# zhili_v1_0.net
KiCad netlist of a schematic drawn in Altium Designer
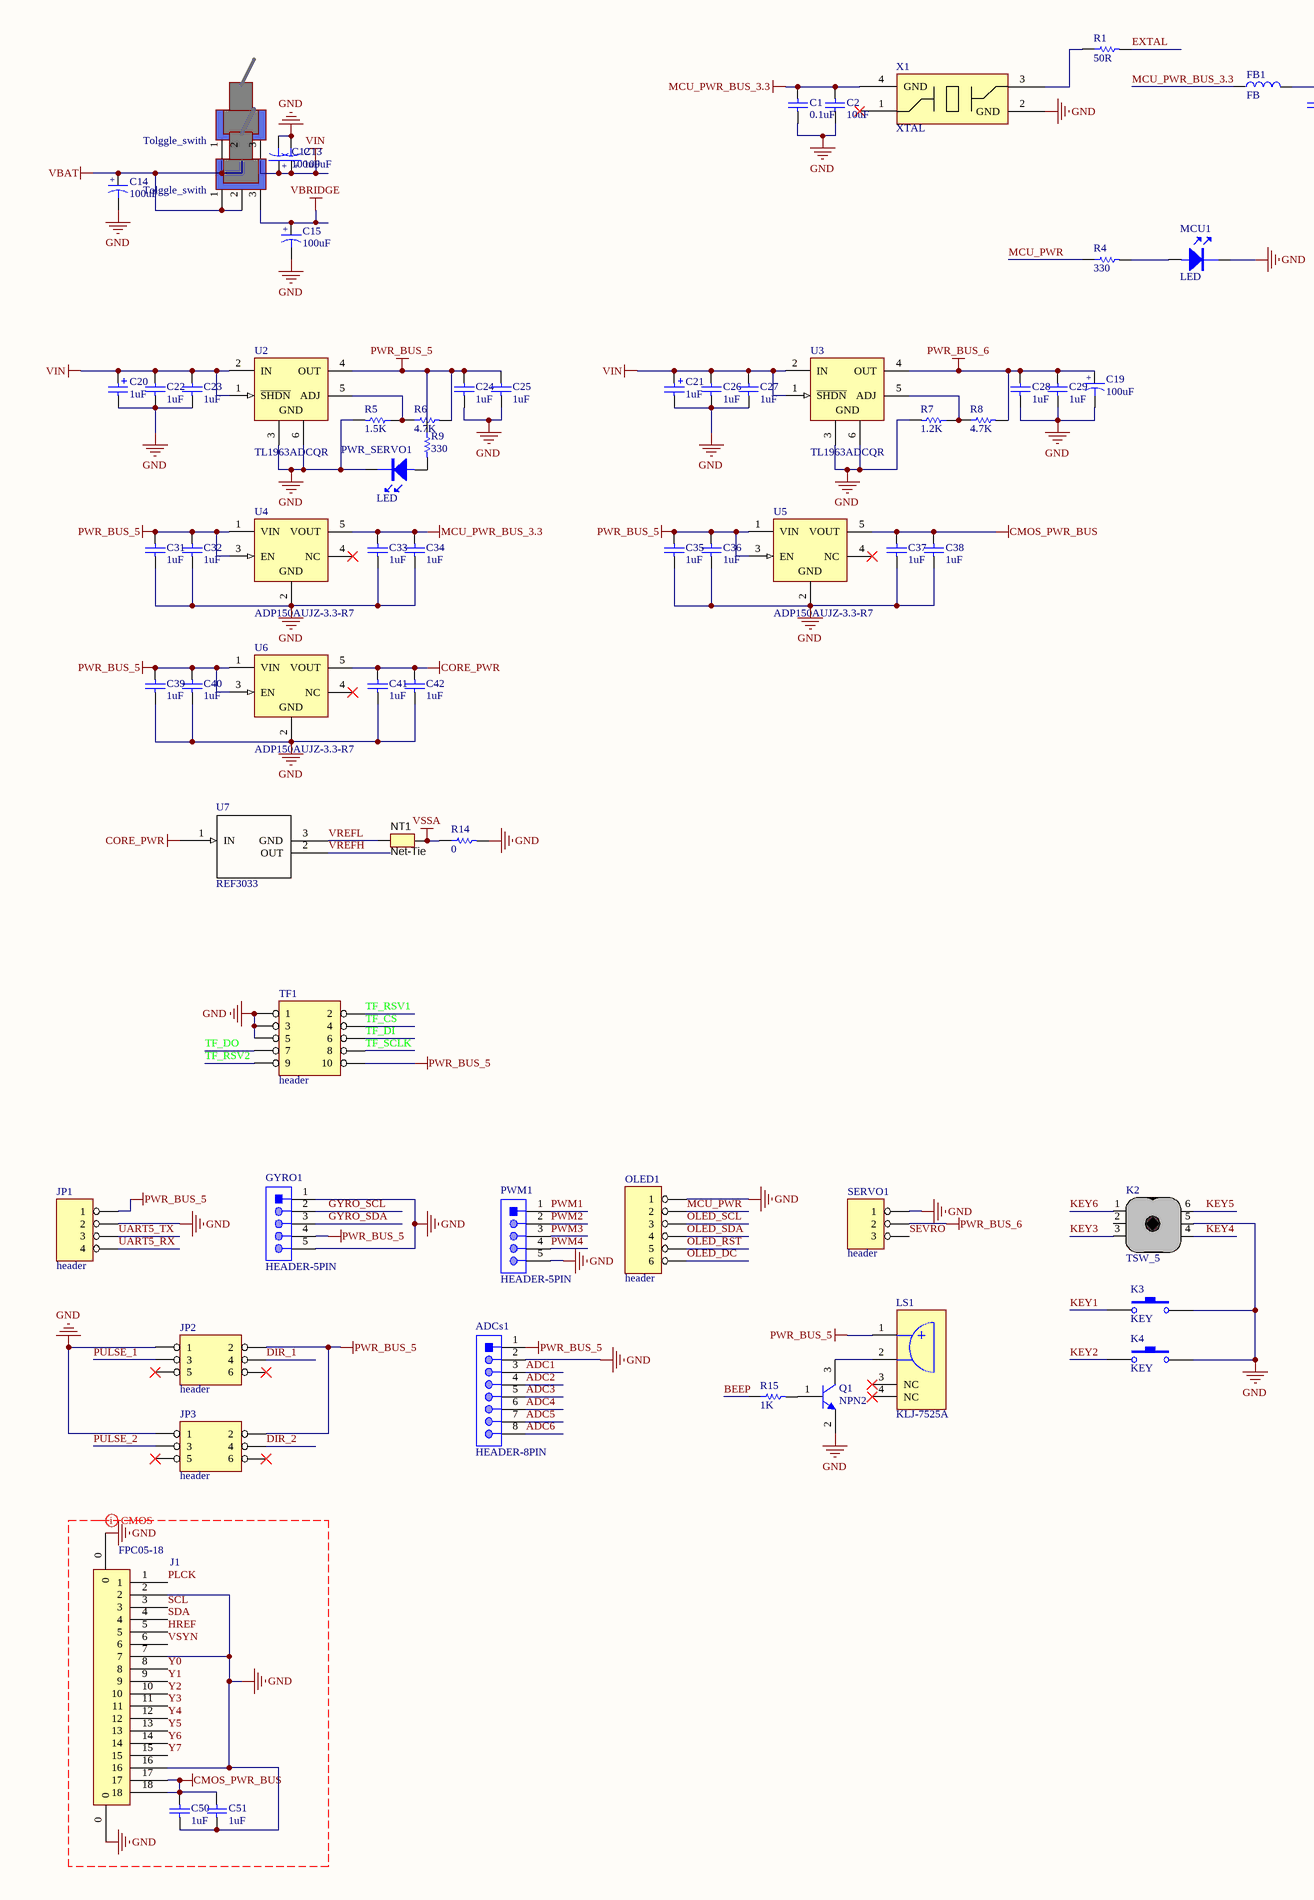
[diagram p0: zhili_v1.0.SchDoc, left]
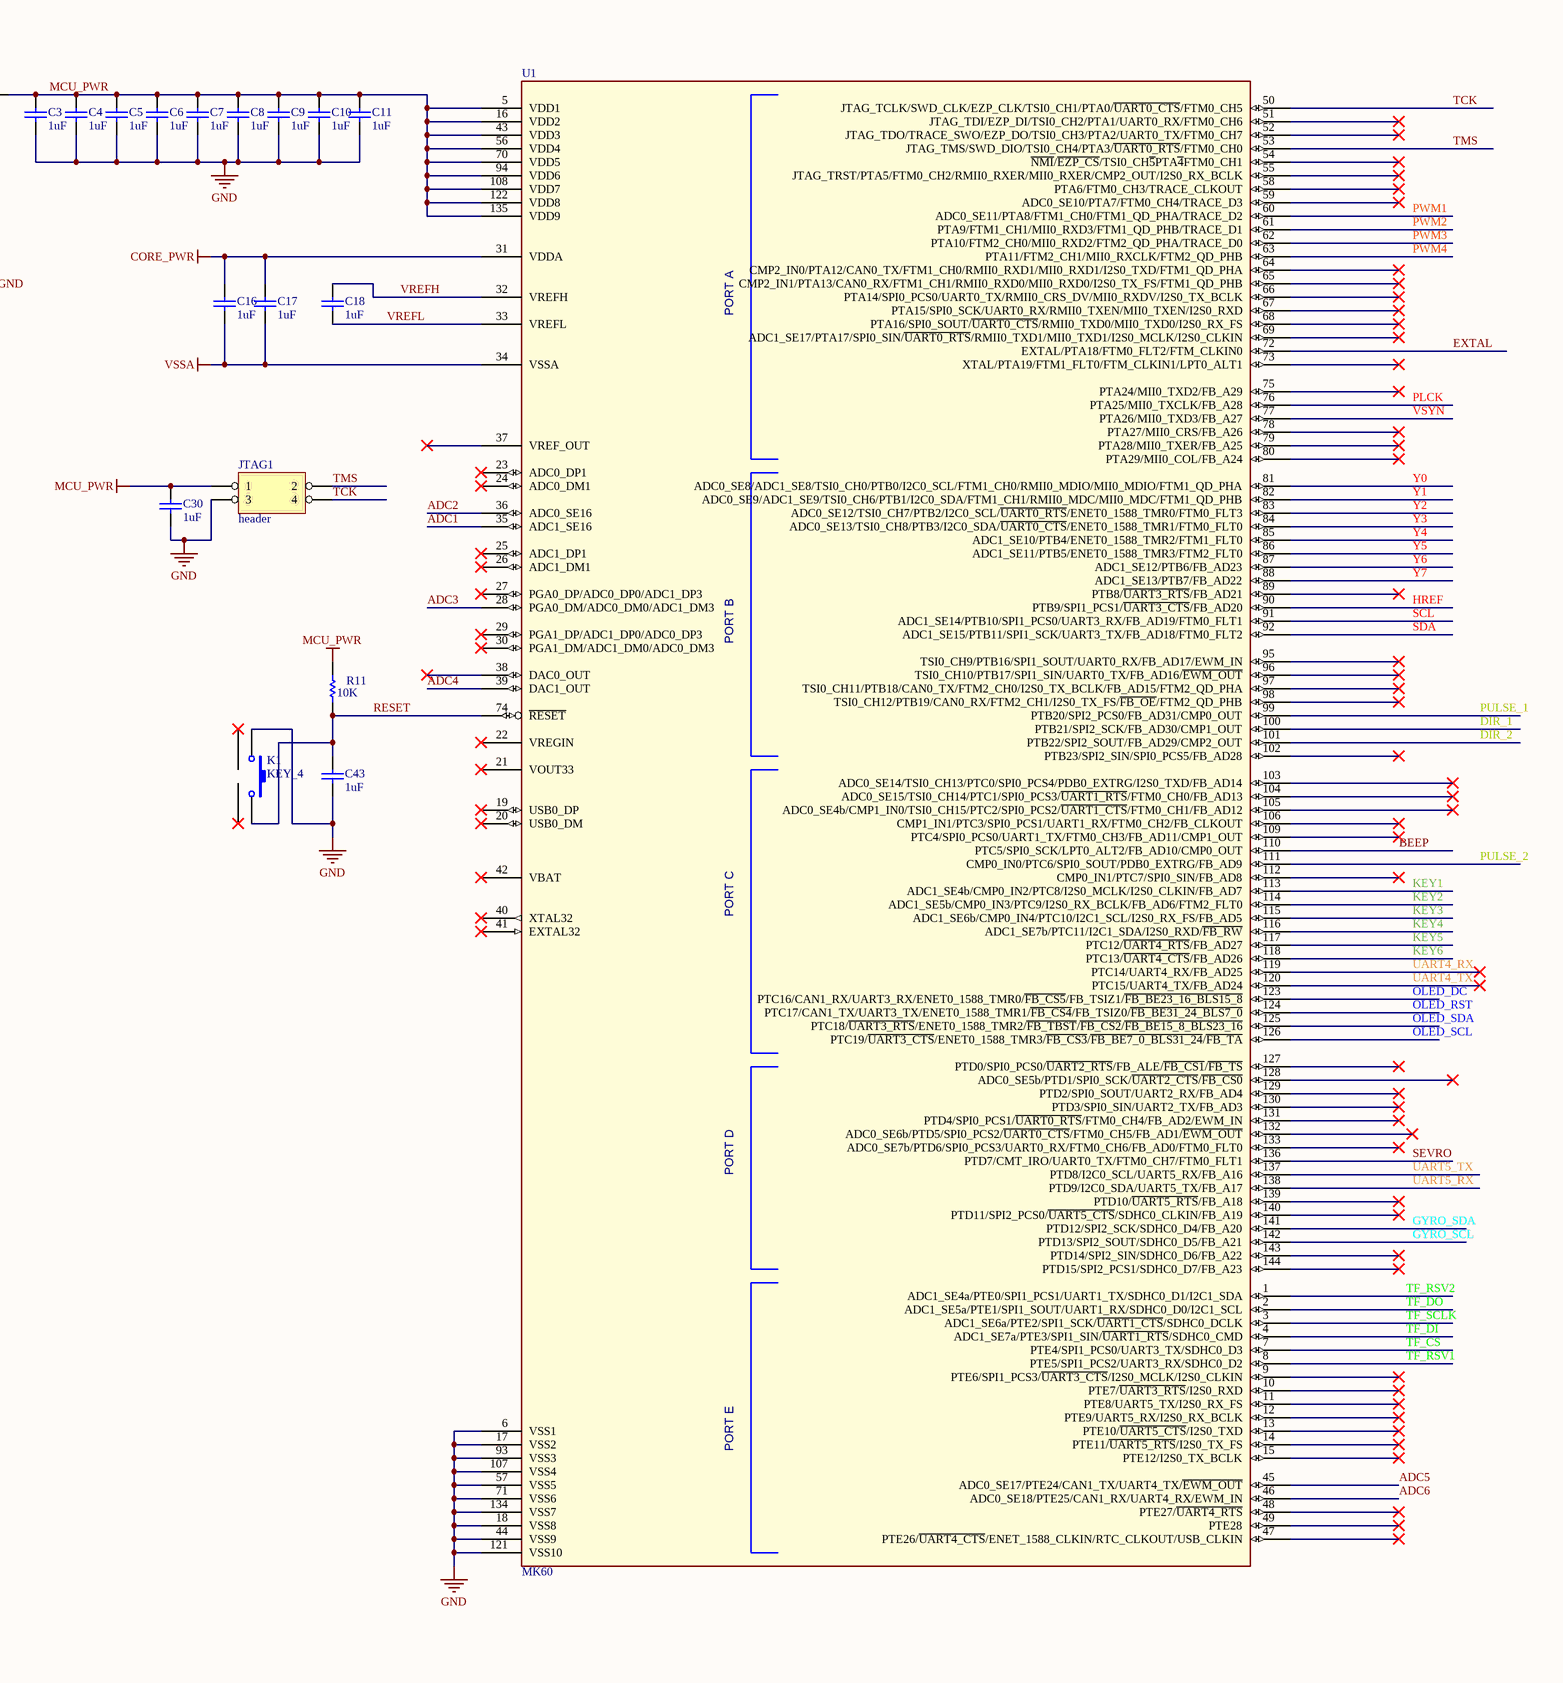
[diagram p1: zhili_v1.0.SchDoc, right]

(export (version "E")
  (design (tool "Eeschema 10.0.6"))
  (components
    (comp (ref "ADCs1")
      (value "HEADER-8PIN")
      (footprint "HEADER_8P_1.25_RT")
      (libsource (lib "My Footprint") (part "HEADER-8PIN"))
    )
    (comp (ref "C1")
      (value "0.1uF")
      (footprint "0603_C")
      (description "Capacitor")
      (fields (field (name "PUBLISHER") "Altium Limited"))
      (libsource (lib "My Footprint") (part "CAP"))
    )
    (comp (ref "C2")
      (value "10uF")
      (footprint "0603_C")
      (description "Capacitor")
      (fields (field (name "PUBLISHER") "Altium Limited"))
      (libsource (lib "My Footprint") (part "CAP"))
    )
    (comp (ref "C3")
      (value "1uF")
      (footprint "0603_C")
      (description "Capacitor")
      (fields (field (name "PUBLISHER") "Altium Limited"))
      (libsource (lib "My Footprint") (part "CAP"))
    )
    (comp (ref "C4")
      (value "1uF")
      (footprint "0603_C")
      (description "Capacitor")
      (fields (field (name "PUBLISHER") "Altium Limited"))
      (libsource (lib "My Footprint") (part "CAP"))
    )
    (comp (ref "C5")
      (value "1uF")
      (footprint "0603_C")
      (description "Capacitor")
      (fields (field (name "PUBLISHER") "Altium Limited"))
      (libsource (lib "My Footprint") (part "CAP"))
    )
    (comp (ref "C6")
      (value "1uF")
      (footprint "0603_C")
      (description "Capacitor")
      (fields (field (name "PUBLISHER") "Altium Limited"))
      (libsource (lib "My Footprint") (part "CAP"))
    )
    (comp (ref "C7")
      (value "1uF")
      (footprint "0603_C")
      (description "Capacitor")
      (fields (field (name "PUBLISHER") "Altium Limited"))
      (libsource (lib "My Footprint") (part "CAP"))
    )
    (comp (ref "C8")
      (value "1uF")
      (footprint "0603_C")
      (description "Capacitor")
      (fields (field (name "PUBLISHER") "Altium Limited"))
      (libsource (lib "My Footprint") (part "CAP"))
    )
    (comp (ref "C9")
      (value "1uF")
      (footprint "0603_C")
      (description "Capacitor")
      (fields (field (name "PUBLISHER") "Altium Limited"))
      (libsource (lib "My Footprint") (part "CAP"))
    )
    (comp (ref "C10")
      (value "1uF")
      (footprint "0603_C")
      (description "Capacitor")
      (fields (field (name "PUBLISHER") "Altium Limited"))
      (libsource (lib "My Footprint") (part "CAP"))
    )
    (comp (ref "C11")
      (value "1uF")
      (footprint "0603_C")
      (description "Capacitor")
      (fields (field (name "PUBLISHER") "Altium Limited"))
      (libsource (lib "My Footprint") (part "CAP"))
    )
    (comp (ref "C12")
      (value "100uF")
      (footprint "C6.3X6.3")
      (libsource (lib "PCB_Project1") (part "Cap_polar"))
    )
    (comp (ref "C13")
      (value "100uF")
      (footprint "C6.3X6.3")
      (libsource (lib "PCB_Project1") (part "Cap_polar"))
    )
    (comp (ref "C14")
      (value "100uF")
      (footprint "CAP 10 x 12")
      (libsource (lib "PCB_Project1") (part "Cap_polar"))
    )
    (comp (ref "C15")
      (value "100uF")
      (footprint "C6.3X6.3")
      (libsource (lib "PCB_Project1") (part "Cap_polar"))
    )
    (comp (ref "C16")
      (value "1uF")
      (footprint "0603_C")
      (description "Capacitor")
      (fields (field (name "PUBLISHER") "Altium Limited"))
      (libsource (lib "My Footprint") (part "CAP"))
    )
    (comp (ref "C17")
      (value "1uF")
      (footprint "0603_C")
      (description "Capacitor")
      (fields (field (name "PUBLISHER") "Altium Limited"))
      (libsource (lib "My Footprint") (part "CAP"))
    )
    (comp (ref "C18")
      (value "1uF")
      (footprint "0603_C")
      (description "Capacitor")
      (fields (field (name "PUBLISHER") "Altium Limited"))
      (libsource (lib "My Footprint") (part "CAP"))
    )
    (comp (ref "C19")
      (value "100uF")
      (footprint "C6.3X6.3")
      (libsource (lib "PCB_Project1") (part "Cap_polar"))
    )
    (comp (ref "C20")
      (value "1uF")
      (footprint "CAPC6032C")
      (description "Capacitor")
      (fields (field (name "PUBLISHER") "Altium Limited"))
      (libsource (lib "My Footprint") (part "CAP_tan"))
    )
    (comp (ref "C21")
      (value "1uF")
      (footprint "CAPC6032C")
      (description "Capacitor")
      (fields (field (name "PUBLISHER") "Altium Limited"))
      (libsource (lib "My Footprint") (part "CAP_tan"))
    )
    (comp (ref "C22")
      (value "1uF")
      (footprint "0603_C")
      (description "Capacitor")
      (fields (field (name "PUBLISHER") "Altium Limited"))
      (libsource (lib "My Footprint") (part "CAP"))
    )
    (comp (ref "C23")
      (value "1uF")
      (footprint "0603_C")
      (description "Capacitor")
      (fields (field (name "PUBLISHER") "Altium Limited"))
      (libsource (lib "My Footprint") (part "CAP"))
    )
    (comp (ref "C24")
      (value "1uF")
      (footprint "0603_C")
      (description "Capacitor")
      (fields (field (name "PUBLISHER") "Altium Limited"))
      (libsource (lib "My Footprint") (part "CAP"))
    )
    (comp (ref "C25")
      (value "1uF")
      (footprint "0603_C")
      (description "Capacitor")
      (fields (field (name "PUBLISHER") "Altium Limited"))
      (libsource (lib "My Footprint") (part "CAP"))
    )
    (comp (ref "C26")
      (value "1uF")
      (footprint "0603_C")
      (description "Capacitor")
      (fields (field (name "PUBLISHER") "Altium Limited"))
      (libsource (lib "My Footprint") (part "CAP"))
    )
    (comp (ref "C27")
      (value "1uF")
      (footprint "0603_C")
      (description "Capacitor")
      (fields (field (name "PUBLISHER") "Altium Limited"))
      (libsource (lib "My Footprint") (part "CAP"))
    )
    (comp (ref "C28")
      (value "1uF")
      (footprint "0603_C")
      (description "Capacitor")
      (fields (field (name "PUBLISHER") "Altium Limited"))
      (libsource (lib "My Footprint") (part "CAP"))
    )
    (comp (ref "C29")
      (value "1uF")
      (footprint "0603_C")
      (description "Capacitor")
      (fields (field (name "PUBLISHER") "Altium Limited"))
      (libsource (lib "My Footprint") (part "CAP"))
    )
    (comp (ref "C30")
      (value "1uF")
      (footprint "0603_C")
      (description "Capacitor")
      (fields (field (name "PUBLISHER") "Altium Limited"))
      (libsource (lib "My Footprint") (part "CAP"))
    )
    (comp (ref "C31")
      (value "1uF")
      (footprint "0805_c")
      (description "Capacitor")
      (fields (field (name "PUBLISHER") "Altium Limited"))
      (libsource (lib "My Footprint") (part "CAP"))
    )
    (comp (ref "C32")
      (value "1uF")
      (footprint "0603_C")
      (description "Capacitor")
      (fields (field (name "PUBLISHER") "Altium Limited"))
      (libsource (lib "My Footprint") (part "CAP"))
    )
    (comp (ref "C33")
      (value "1uF")
      (footprint "0805_c")
      (description "Capacitor")
      (fields (field (name "PUBLISHER") "Altium Limited"))
      (libsource (lib "My Footprint") (part "CAP"))
    )
    (comp (ref "C34")
      (value "1uF")
      (footprint "0603_C")
      (description "Capacitor")
      (fields (field (name "PUBLISHER") "Altium Limited"))
      (libsource (lib "My Footprint") (part "CAP"))
    )
    (comp (ref "C35")
      (value "1uF")
      (footprint "0805_c")
      (description "Capacitor")
      (fields (field (name "PUBLISHER") "Altium Limited"))
      (libsource (lib "My Footprint") (part "CAP"))
    )
    (comp (ref "C36")
      (value "1uF")
      (footprint "0603_C")
      (description "Capacitor")
      (fields (field (name "PUBLISHER") "Altium Limited"))
      (libsource (lib "My Footprint") (part "CAP"))
    )
    (comp (ref "C37")
      (value "1uF")
      (footprint "0805_c")
      (description "Capacitor")
      (fields (field (name "PUBLISHER") "Altium Limited"))
      (libsource (lib "My Footprint") (part "CAP"))
    )
    (comp (ref "C38")
      (value "1uF")
      (footprint "0603_C")
      (description "Capacitor")
      (fields (field (name "PUBLISHER") "Altium Limited"))
      (libsource (lib "My Footprint") (part "CAP"))
    )
    (comp (ref "C39")
      (value "1uF")
      (footprint "0805_c")
      (description "Capacitor")
      (fields (field (name "PUBLISHER") "Altium Limited"))
      (libsource (lib "My Footprint") (part "CAP"))
    )
    (comp (ref "C40")
      (value "1uF")
      (footprint "0603_C")
      (description "Capacitor")
      (fields (field (name "PUBLISHER") "Altium Limited"))
      (libsource (lib "My Footprint") (part "CAP"))
    )
    (comp (ref "C41")
      (value "1uF")
      (footprint "0805_c")
      (description "Capacitor")
      (fields (field (name "PUBLISHER") "Altium Limited"))
      (libsource (lib "My Footprint") (part "CAP"))
    )
    (comp (ref "C42")
      (value "1uF")
      (footprint "0603_C")
      (description "Capacitor")
      (fields (field (name "PUBLISHER") "Altium Limited"))
      (libsource (lib "My Footprint") (part "CAP"))
    )
    (comp (ref "C43")
      (value "1uF")
      (footprint "0603_C")
      (description "Capacitor")
      (fields (field (name "PUBLISHER") "Altium Limited"))
      (libsource (lib "My Footprint") (part "CAP"))
    )
    (comp (ref "C50")
      (value "1uF")
      (footprint "0603_C")
      (description "Capacitor")
      (fields (field (name "PUBLISHER") "Altium Limited"))
      (libsource (lib "My Footprint") (part "CAP"))
    )
    (comp (ref "C51")
      (value "1uF")
      (footprint "0603_C")
      (description "Capacitor")
      (fields (field (name "PUBLISHER") "Altium Limited"))
      (libsource (lib "My Footprint") (part "CAP"))
    )
    (comp (ref "DRV1")
      (value "Tolggle_swith")
      (footprint "TOGGLE SWICH STAND")
      (libsource (lib "通用驱动") (part "Tolggle_swith"))
    )
    (comp (ref "FB1")
      (value "FB")
      (footprint "0805")
      (description "磁珠")
      (libsource (lib "My Footprint") (part "FB"))
    )
    (comp (ref "GYRO1")
      (value "HEADER-5PIN")
      (footprint "HEADER_5P_1.25_RT")
      (libsource (lib "My Footprint") (part "HEADER-5PIN"))
    )
    (comp (ref "J1") (value "FPC05-18") (footprint "FPC_18_VER") (libsource (lib "FPC18") (part "FPC05-18")))
    (comp (ref "JP1")
      (value "header")
      (footprint "header4")
      (libsource (lib "My Footprint") (part "HEADER 4"))
    )
    (comp (ref "JP2")
      (value "header")
      (footprint "header2X3")
      (libsource (lib "My Footprint") (part "HEADER 3X2"))
    )
    (comp (ref "JP3")
      (value "header")
      (footprint "header2X3")
      (libsource (lib "My Footprint") (part "HEADER 3X2"))
    )
    (comp (ref "JTAG1")
      (value "header")
      (footprint "header_2x2_1.27")
      (libsource (lib "My Footprint") (part "HEADER 2X2"))
    )
    (comp (ref "K1")
      (value "KEY_4")
      (footprint "KEY5*5")
      (description "Switch")
      (fields (field (name "PUBLISHER") "Altium Limited"))
      (libsource (lib "My Footprint") (part "KEY_4"))
    )
    (comp (ref "K2")
      (value "TSW_5")
      (footprint "TSW-10")
      (description "方向开关")
      (libsource (lib "My Footprint") (part "TSW_5"))
    )
    (comp (ref "K3")
      (value "KEY")
      (footprint "KEY_2")
      (description "Switch")
      (fields (field (name "PUBLISHER") "Altium Limited"))
      (libsource (lib "My Footprint") (part "KEY_2"))
    )
    (comp (ref "K4")
      (value "KEY")
      (footprint "KEY_2")
      (description "Switch")
      (fields (field (name "PUBLISHER") "Altium Limited"))
      (libsource (lib "My Footprint") (part "KEY_2"))
    )
    (comp (ref "LS1")
      (value "KLJ-7525A")
      (footprint "KLJ-7525A_V")
      (fields (field (name "MANUFACTURER") "KaiLiJin"))
      (libsource (lib "Altium Content Vault") (part "KLJ-7525A-4"))
    )
    (comp (ref "MBD1")
      (value "Tolggle_swith")
      (footprint "TOGGLE SWICH STAND")
      (libsource (lib "通用驱动") (part "Tolggle_swith"))
    )
    (comp (ref "MCU1")
      (value "LED")
      (footprint "0603_LED")
      (description "LED 发光二极管")
      (libsource (lib "My Footprint") (part "LED"))
    )
    (comp (ref "NT1")
      (value "Net-Tie")
      (footprint "Net-Tie_10mil")
      (description "Single point connection between nets.")
      (fields (field (name "SYMBOLCREATOR") "codlsc") (field (name "PUBLISHER") "Texas Instruments"))
      (libsource (lib "My Footprint") (part "Net-Tie"))
    )
    (comp (ref "OLED1")
      (value "header")
      (footprint "0.96寸OLED模块")
      (libsource (lib "My Footprint") (part "HEADER 6"))
    )
    (comp (ref "PWM1")
      (value "HEADER-5PIN")
      (footprint "HEADER_5P_1.25_RT")
      (libsource (lib "My Footprint") (part "HEADER-5PIN"))
    )
    (comp (ref "PWR_SERVO1")
      (value "LED")
      (footprint "0805_LED")
      (description "LED 发光二极管")
      (libsource (lib "My Footprint") (part "LED"))
    )
    (comp (ref "Q1")
      (value "NPN2")
      (footprint "SOT-23-3")
      (description "贴片")
      (libsource (lib "My Footprint") (part "NPN2"))
    )
    (comp (ref "R1")
      (value "50R")
      (footprint "0603_R")
      (description "Resistor")
      (fields (field (name "PUBLISHER") "Altium Limited"))
      (libsource (lib "My Footprint") (part "RES"))
    )
    (comp (ref "R4")
      (value "330")
      (footprint "0603_R")
      (description "Resistor")
      (fields (field (name "PUBLISHER") "Altium Limited"))
      (libsource (lib "My Footprint") (part "RES"))
    )
    (comp (ref "R5")
      (value "1.5K")
      (footprint "0603_R")
      (description "Resistor")
      (fields (field (name "PUBLISHER") "Altium Limited"))
      (libsource (lib "My Footprint") (part "RES"))
    )
    (comp (ref "R6")
      (value "4.7K")
      (footprint "0603_R")
      (description "Resistor")
      (fields (field (name "PUBLISHER") "Altium Limited"))
      (libsource (lib "My Footprint") (part "RES"))
    )
    (comp (ref "R7")
      (value "1.2K")
      (footprint "0603_R")
      (description "Resistor")
      (fields (field (name "PUBLISHER") "Altium Limited"))
      (libsource (lib "My Footprint") (part "RES"))
    )
    (comp (ref "R8")
      (value "4.7K")
      (footprint "0603_R")
      (description "Resistor")
      (fields (field (name "PUBLISHER") "Altium Limited"))
      (libsource (lib "My Footprint") (part "RES"))
    )
    (comp (ref "R9")
      (value "330")
      (footprint "0603_R")
      (description "Resistor")
      (fields (field (name "PUBLISHER") "Altium Limited"))
      (libsource (lib "My Footprint") (part "RES"))
    )
    (comp (ref "R11")
      (value "10K")
      (footprint "0603_R")
      (description "Resistor")
      (fields (field (name "PUBLISHER") "Altium Limited"))
      (libsource (lib "My Footprint") (part "RES"))
    )
    (comp (ref "R14")
      (value "0")
      (footprint "0603_R")
      (description "Resistor")
      (fields (field (name "PUBLISHER") "Altium Limited"))
      (libsource (lib "My Footprint") (part "RES"))
    )
    (comp (ref "R15")
      (value "1K")
      (footprint "0603_R")
      (description "Resistor")
      (fields (field (name "PUBLISHER") "Altium Limited"))
      (libsource (lib "My Footprint") (part "RES"))
    )
    (comp (ref "SERVO1")
      (value "header")
      (footprint "header3")
      (libsource (lib "My Footprint") (part "HEADER 3"))
    )
    (comp (ref "TF1")
      (value "header")
      (footprint "2002132100010C4LF")
      (libsource (lib "My Footprint") (part "HEADER 5X2"))
    )
    (comp (ref "U1") (value "MK60") (footprint "LQFP144") (libsource (lib "My Footprint") (part "MK60")))
    (comp (ref "U2")
      (value "TL1963ADCQR")
      (footprint "DCQ0006A_M")
      (fields (field (name "MANUFACTURER") "Texas Instruments"))
      (libsource (lib "Altium Content Vault") (part "TI-TPS7A4501_TL1963A-6"))
    )
    (comp (ref "U3")
      (value "TL1963ADCQR")
      (footprint "DCQ0006A_M")
      (fields (field (name "MANUFACTURER") "Texas Instruments"))
      (libsource (lib "Altium Content Vault") (part "TI-TPS7A4501_TL1963A-6"))
    )
    (comp (ref "U4")
      (value "ADP150AUJZ-3.3-R7")
      (footprint "ADI-UJ-5_M")
      (fields (field (name "MANUFACTURER") "Analog Devices"))
      (libsource (lib "Altium Content Vault") (part "ADI-ADP1XX-UJ-5"))
    )
    (comp (ref "U5")
      (value "ADP150AUJZ-3.3-R7")
      (footprint "ADI-UJ-5_M")
      (fields (field (name "MANUFACTURER") "Analog Devices"))
      (libsource (lib "Altium Content Vault") (part "ADI-ADP1XX-UJ-5"))
    )
    (comp (ref "U6")
      (value "ADP150AUJZ-3.3-R7")
      (footprint "ADI-UJ-5_M")
      (fields (field (name "MANUFACTURER") "Analog Devices"))
      (libsource (lib "Altium Content Vault") (part "ADI-ADP1XX-UJ-5"))
    )
    (comp (ref "U7")
      (value "REF3033")
      (footprint "SOT-23-3")
      (description "Imported")
      (fields
        (field (name "MANUFACTURER") "Texas Instruments")
        (field (name "MANUFACTURER_PART_NUMBER") "ref3033_dbz_3")
      )
      (libsource (lib "My Footprint") (part "REF3033_DBZ_3"))
    )
    (comp (ref "X1")
      (value "XTAL")
      (footprint "OSC_KH3225_4P")
      (libsource (lib "My Footprint") (part "XTAL_贴片"))
    )
  )
  (nets
    (net (code "1") (name "/ADC1") (class "Default")
      (node (ref "ADCs1") (pin "3") (pinfunction "3_3") (pintype "passive"))
      (node (ref "U1") (pin "35") (pinfunction "ADC1_SE16_35") (pintype "bidirectional"))
    )
    (net (code "2") (name "/ADC2") (class "Default")
      (node (ref "ADCs1") (pin "4") (pinfunction "4_4") (pintype "passive"))
      (node (ref "U1") (pin "36") (pinfunction "ADC0_SE16_36") (pintype "bidirectional"))
    )
    (net (code "3") (name "/ADC3") (class "Default")
      (node (ref "ADCs1") (pin "5") (pinfunction "5_5") (pintype "passive"))
      (node (ref "U1") (pin "28") (pinfunction "PGA0_DM/ADC0_DM0/ADC1_DM3_28") (pintype "bidirectional"))
    )
    (net (code "4") (name "/ADC4") (class "Default")
      (node (ref "ADCs1") (pin "6") (pinfunction "6_6") (pintype "passive"))
      (node (ref "U1") (pin "39") (pinfunction "DAC1_OUT_39") (pintype "bidirectional"))
    )
    (net (code "5") (name "/ADC5") (class "Default")
      (node (ref "ADCs1") (pin "7") (pinfunction "7_7") (pintype "passive"))
      (node (ref "U1") (pin "45") (pinfunction "ADC0_SE17/PTE24/CAN1_TX/UART4_TX/~{EWM_OUT}_45") (pintype "bidirectional"))
    )
    (net (code "6") (name "/ADC6") (class "Default")
      (node (ref "ADCs1") (pin "8") (pinfunction "8_8") (pintype "passive"))
      (node (ref "U1") (pin "46") (pinfunction "ADC0_SE18/PTE25/CAN1_RX/UART4_RX/EWM_IN_46") (pintype "bidirectional"))
    )
    (net (code "7") (name "/BEEP") (class "Default")
      (node (ref "R15") (pin "1") (pinfunction "1_1") (pintype "passive"))
      (node (ref "U1") (pin "110") (pinfunction "PTC5/SPI0_SCK/LPT0_ALT2/FB_AD10/CMP0_OUT_110") (pintype "bidirectional"))
    )
    (net (code "8") (name "/DIR_1") (class "Default")
      (node (ref "JP2") (pin "4") (pinfunction "4_4") (pintype "passive"))
      (node (ref "U1") (pin "100") (pinfunction "PTB21/SPI2_SCK/FB_AD30/CMP1_OUT_100") (pintype "bidirectional"))
    )
    (net (code "9") (name "/DIR_2") (class "Default")
      (node (ref "JP3") (pin "4") (pinfunction "4_4") (pintype "passive"))
      (node (ref "U1") (pin "101") (pinfunction "PTB22/SPI2_SOUT/FB_AD29/CMP2_OUT_101") (pintype "bidirectional"))
    )
    (net (code "10") (name "/EXTAL") (class "Default")
      (node (ref "R1") (pin "2") (pinfunction "2_2") (pintype "passive"))
      (node (ref "U1") (pin "72") (pinfunction "EXTAL/PTA18/FTM0_FLT2/FTM_CLKIN0_72") (pintype "bidirectional"))
    )
    (net (code "11") (name "/GYRO_SCL") (class "Default")
      (node (ref "GYRO1") (pin "2") (pinfunction "2_2") (pintype "passive"))
      (node (ref "U1") (pin "142") (pinfunction "PTD13/SPI2_SOUT/SDHC0_D5/FB_A21_142") (pintype "bidirectional"))
    )
    (net (code "12") (name "/GYRO_SDA") (class "Default")
      (node (ref "GYRO1") (pin "3") (pinfunction "3_3") (pintype "passive"))
      (node (ref "U1") (pin "141") (pinfunction "PTD12/SPI2_SCK/SDHC0_D4/FB_A20_141") (pintype "bidirectional"))
    )
    (net (code "13") (name "/HREF") (class "Default")
      (node (ref "J1") (pin "5") (pinfunction "5_5") (pintype "passive"))
      (node (ref "U1") (pin "90") (pinfunction "PTB9/SPI1_PCS1/~{UART3_CTS}/FB_AD20_90") (pintype "bidirectional"))
    )
    (net (code "14") (name "/KEY1") (class "Default")
      (node (ref "K3") (pin "1") (pinfunction "1_1") (pintype "passive"))
      (node (ref "U1") (pin "113") (pinfunction "ADC1_SE4b/CMP0_IN2/PTC8/I2S0_MCLK/I2S0_CLKIN/FB_AD7_113") (pintype "bidirectional"))
    )
    (net (code "15") (name "/KEY2") (class "Default")
      (node (ref "K4") (pin "1") (pinfunction "1_1") (pintype "passive"))
      (node (ref "U1") (pin "114") (pinfunction "ADC1_SE5b/CMP0_IN3/PTC9/I2S0_RX_BCLK/FB_AD6/FTM2_FLT0_114") (pintype "bidirectional"))
    )
    (net (code "16") (name "/KEY3") (class "Default")
      (node (ref "K2") (pin "3") (pintype "passive"))
      (node (ref "U1") (pin "115") (pinfunction "ADC1_SE6b/CMP0_IN4/PTC10/I2C1_SCL/I2S0_RX_FS/FB_AD5_115") (pintype "bidirectional"))
    )
    (net (code "17") (name "/KEY4") (class "Default")
      (node (ref "K2") (pin "4") (pintype "passive"))
      (node (ref "U1") (pin "116") (pinfunction "ADC1_SE7b/PTC11/I2C1_SDA/I2S0_RXD/~{FB_RW}_116") (pintype "bidirectional"))
    )
    (net (code "18") (name "/KEY5") (class "Default")
      (node (ref "K2") (pin "6") (pintype "passive"))
      (node (ref "U1") (pin "117") (pinfunction "PTC12/~{UART4_RTS}/FB_AD27_117") (pintype "bidirectional"))
    )
    (net (code "19") (name "/KEY6") (class "Default")
      (node (ref "K2") (pin "1") (pintype "passive"))
      (node (ref "U1") (pin "118") (pinfunction "PTC13/~{UART4_CTS}/FB_AD26_118") (pintype "bidirectional"))
    )
    (net (code "20") (name "/OLED_DC") (class "Default")
      (node (ref "OLED1") (pin "6") (pinfunction "6_6") (pintype "passive"))
      (node (ref "U1") (pin "123") (pinfunction "PTC16/CAN1_RX/UART3_RX/ENET0_1588_TMR0/~{FB_CS5}/FB_TSIZ1/~{FB_BE23_16_BLS15_8}_123") (pintype "bidirectional"))
    )
    (net (code "21") (name "/OLED_RST") (class "Default")
      (node (ref "OLED1") (pin "5") (pinfunction "5_5") (pintype "passive"))
      (node (ref "U1") (pin "124") (pinfunction "PTC17/CAN1_TX/UART3_TX/ENET0_1588_TMR1/~{FB_CS4}/FB_TSIZ0/~{FB_BE31_24_BLS7_0}_124") (pintype "bidirectional"))
    )
    (net (code "22") (name "/OLED_SCL") (class "Default")
      (node (ref "OLED1") (pin "3") (pinfunction "3_3") (pintype "passive"))
      (node (ref "U1") (pin "126") (pinfunction "PTC19/~{UART3_CTS}/ENET0_1588_TMR3/~{FB_CS3}/~{FB_BE7_0_BLS31_24}/~{FB_TA}_126") (pintype "bidirectional"))
    )
    (net (code "23") (name "/OLED_SDA") (class "Default")
      (node (ref "OLED1") (pin "4") (pinfunction "4_4") (pintype "passive"))
      (node (ref "U1") (pin "125") (pinfunction "PTC18/~{UART3_RTS}/ENET0_1588_TMR2/~{FB_TBST}/~{FB_CS2}/~{FB_BE15_8_BLS23_16}_125") (pintype "bidirectional"))
    )
    (net (code "24") (name "/PLCK") (class "Default")
      (node (ref "J1") (pin "1") (pinfunction "1_1") (pintype "passive"))
      (node (ref "U1") (pin "76") (pinfunction "PTA25/MII0_TXCLK/FB_A28_76") (pintype "bidirectional"))
    )
    (net (code "25") (name "/PULSE_1") (class "Default")
      (node (ref "JP2") (pin "3") (pinfunction "3_3") (pintype "passive"))
      (node (ref "U1") (pin "99") (pinfunction "PTB20/SPI2_PCS0/FB_AD31/CMP0_OUT_99") (pintype "bidirectional"))
    )
    (net (code "26") (name "/PULSE_2") (class "Default")
      (node (ref "JP3") (pin "3") (pinfunction "3_3") (pintype "passive"))
      (node (ref "U1") (pin "111") (pinfunction "CMP0_IN0/PTC6/SPI0_SOUT/PDB0_EXTRG/FB_AD9_111") (pintype "bidirectional"))
    )
    (net (code "27") (name "/PWM1") (class "Default")
      (node (ref "PWM1") (pin "1") (pinfunction "1_1") (pintype "passive"))
      (node (ref "U1") (pin "60") (pinfunction "ADC0_SE11/PTA8/FTM1_CH0/FTM1_QD_PHA/TRACE_D2_60") (pintype "bidirectional"))
    )
    (net (code "28") (name "/PWM2") (class "Default")
      (node (ref "PWM1") (pin "2") (pinfunction "2_2") (pintype "passive"))
      (node (ref "U1") (pin "61") (pinfunction "PTA9/FTM1_CH1/MII0_RXD3/FTM1_QD_PHB/TRACE_D1_61") (pintype "bidirectional"))
    )
    (net (code "29") (name "/PWM3") (class "Default")
      (node (ref "PWM1") (pin "3") (pinfunction "3_3") (pintype "passive"))
      (node (ref "U1") (pin "62") (pinfunction "PTA10/FTM2_CH0/MII0_RXD2/FTM2_QD_PHA/TRACE_D0_62") (pintype "bidirectional"))
    )
    (net (code "30") (name "/PWM4") (class "Default")
      (node (ref "PWM1") (pin "4") (pinfunction "4_4") (pintype "passive"))
      (node (ref "U1") (pin "63") (pinfunction "PTA11/FTM2_CH1/MII0_RXCLK/FTM2_QD_PHB_63") (pintype "bidirectional"))
    )
    (net (code "31") (name "/RESET") (class "Default")
      (node (ref "C43") (pin "2") (pinfunction "2_2") (pintype "passive"))
      (node (ref "K1") (pin "2") (pinfunction "2_2") (pintype "passive"))
      (node (ref "R11") (pin "1") (pinfunction "1_1") (pintype "passive"))
      (node (ref "U1") (pin "74") (pinfunction "~{RESET}_74") (pintype "bidirectional"))
    )
    (net (code "32") (name "/SCL") (class "Default")
      (node (ref "J1") (pin "3") (pinfunction "3_3") (pintype "passive"))
      (node (ref "U1") (pin "91") (pinfunction "ADC1_SE14/PTB10/SPI1_PCS0/UART3_RX/FB_AD19/FTM0_FLT1_91") (pintype "bidirectional"))
    )
    (net (code "33") (name "/SDA") (class "Default")
      (node (ref "J1") (pin "4") (pinfunction "4_4") (pintype "passive"))
      (node (ref "U1") (pin "92") (pinfunction "ADC1_SE15/PTB11/SPI1_SCK/UART3_TX/FB_AD18/FTM0_FLT2_92") (pintype "bidirectional"))
    )
    (net (code "34") (name "/SEVRO") (class "Default")
      (node (ref "SERVO1") (pin "3") (pinfunction "3_3") (pintype "passive"))
      (node (ref "U1") (pin "136") (pinfunction "PTD7/CMT_IRO/UART0_TX/FTM0_CH7/FTM0_FLT1_136") (pintype "bidirectional"))
    )
    (net (code "35") (name "/TCK") (class "Default")
      (node (ref "JTAG1") (pin "4") (pinfunction "4_4") (pintype "passive"))
      (node (ref "U1") (pin "50") (pinfunction "JTAG_TCLK/SWD_CLK/EZP_CLK/TSI0_CH1/PTA0/~{UART0_CTS}/FTM0_CH5_50") (pintype "bidirectional"))
    )
    (net (code "36") (name "/TF_CS") (class "Default")
      (node (ref "TF1") (pin "4") (pinfunction "4_4") (pintype "passive"))
      (node (ref "U1") (pin "7") (pinfunction "PTE4/SPI1_PCS0/UART3_TX/SDHC0_D3_7") (pintype "bidirectional"))
    )
    (net (code "37") (name "/TF_DI") (class "Default")
      (node (ref "TF1") (pin "6") (pinfunction "6_6") (pintype "passive"))
      (node (ref "U1") (pin "4") (pinfunction "ADC1_SE7a/PTE3/SPI1_SIN/~{UART1_RTS}/SDHC0_CMD_4") (pintype "bidirectional"))
    )
    (net (code "38") (name "/TF_DO") (class "Default")
      (node (ref "TF1") (pin "7") (pinfunction "7_7") (pintype "passive"))
      (node (ref "U1") (pin "2") (pinfunction "ADC1_SE5a/PTE1/SPI1_SOUT/UART1_RX/SDHC0_D0/I2C1_SCL_2") (pintype "bidirectional"))
    )
    (net (code "39") (name "/TF_RSV1") (class "Default")
      (node (ref "TF1") (pin "2") (pinfunction "2_2") (pintype "passive"))
      (node (ref "U1") (pin "8") (pinfunction "PTE5/SPI1_PCS2/UART3_RX/SDHC0_D2_8") (pintype "bidirectional"))
    )
    (net (code "40") (name "/TF_RSV2") (class "Default")
      (node (ref "TF1") (pin "9") (pinfunction "9_9") (pintype "passive"))
      (node (ref "U1") (pin "1") (pinfunction "ADC1_SE4a/PTE0/SPI1_PCS1/UART1_TX/SDHC0_D1/I2C1_SDA_1") (pintype "bidirectional"))
    )
    (net (code "41") (name "/TF_SCLK") (class "Default")
      (node (ref "TF1") (pin "8") (pinfunction "8_8") (pintype "passive"))
      (node (ref "U1") (pin "3") (pinfunction "ADC1_SE6a/PTE2/SPI1_SCK/~{UART1_CTS}/SDHC0_DCLK_3") (pintype "bidirectional"))
    )
    (net (code "42") (name "/TMS") (class "Default")
      (node (ref "JTAG1") (pin "2") (pinfunction "2_2") (pintype "passive"))
      (node (ref "U1") (pin "53") (pinfunction "JTAG_TMS/SWD_DIO/TSI0_CH4/PTA3/~{UART0_RTS}/FTM0_CH0_53") (pintype "bidirectional"))
    )
    (net (code "43") (name "/UART4_RX") (class "Default")
      (node (ref "U1") (pin "119") (pinfunction "PTC14/UART4_RX/FB_AD25_119") (pintype "bidirectional+no_connect"))
    )
    (net (code "44") (name "/UART4_TX") (class "Default")
      (node (ref "U1") (pin "120") (pinfunction "PTC15/UART4_TX/FB_AD24_120") (pintype "bidirectional+no_connect"))
    )
    (net (code "45") (name "/UART5_RX") (class "Default")
      (node (ref "JP1") (pin "4") (pinfunction "4_4") (pintype "passive"))
      (node (ref "U1") (pin "138") (pinfunction "PTD9/I2C0_SDA/UART5_TX/FB_A17_138") (pintype "bidirectional"))
    )
    (net (code "46") (name "/UART5_TX") (class "Default")
      (node (ref "JP1") (pin "3") (pinfunction "3_3") (pintype "passive"))
      (node (ref "U1") (pin "137") (pinfunction "PTD8/I2C0_SCL/UART5_RX/FB_A16_137") (pintype "bidirectional"))
    )
    (net (code "47") (name "/VREFH") (class "Default")
      (node (ref "C18") (pin "2") (pinfunction "2_2") (pintype "passive"))
      (node (ref "U1") (pin "32") (pinfunction "VREFH_32") (pintype "power_in"))
      (node (ref "U7") (pin "2") (pinfunction "OUT_2") (pintype "passive"))
    )
    (net (code "48") (name "/VREFL") (class "Default")
      (node (ref "C18") (pin "1") (pinfunction "1_1") (pintype "passive"))
      (node (ref "NT1") (pin "1") (pinfunction "1_1") (pintype "passive"))
      (node (ref "U1") (pin "33") (pinfunction "VREFL_33") (pintype "power_in"))
      (node (ref "U7") (pin "3") (pinfunction "GND_3") (pintype "power_in"))
    )
    (net (code "49") (name "/VSYN") (class "Default")
      (node (ref "J1") (pin "6") (pinfunction "6_6") (pintype "passive"))
      (node (ref "U1") (pin "77") (pinfunction "PTA26/MII0_TXD3/FB_A27_77") (pintype "bidirectional"))
    )
    (net (code "50") (name "/Y0") (class "Default")
      (node (ref "J1") (pin "8") (pinfunction "8_8") (pintype "passive"))
      (node (ref "U1") (pin "81") (pinfunction "ADC0_SE8/ADC1_SE8/TSI0_CH0/PTB0/I2C0_SCL/FTM1_CH0/RMII0_MDIO/MII0_MDIO/FTM1_QD_PHA_81") (pintype "bidirectional"))
    )
    (net (code "51") (name "/Y1") (class "Default")
      (node (ref "J1") (pin "9") (pinfunction "9_9") (pintype "passive"))
      (node (ref "U1") (pin "82") (pinfunction "ADC0_SE9/ADC1_SE9/TSI0_CH6/PTB1/I2C0_SDA/FTM1_CH1/RMII0_MDC/MII0_MDC/FTM1_QD_PHB_82") (pintype "bidirectional"))
    )
    (net (code "52") (name "/Y2") (class "Default")
      (node (ref "J1") (pin "10") (pinfunction "10_10") (pintype "passive"))
      (node (ref "U1") (pin "83") (pinfunction "ADC0_SE12/TSI0_CH7/PTB2/I2C0_SCL/~{UART0_RTS}/ENET0_1588_TMR0/FTM0_FLT3_83") (pintype "bidirectional"))
    )
    (net (code "53") (name "/Y3") (class "Default")
      (node (ref "J1") (pin "11") (pinfunction "11_11") (pintype "passive"))
      (node (ref "U1") (pin "84") (pinfunction "ADC0_SE13/TSI0_CH8/PTB3/I2C0_SDA/~{UART0_CTS}/ENET0_1588_TMR1/FTM0_FLT0_84") (pintype "bidirectional"))
    )
    (net (code "54") (name "/Y4") (class "Default")
      (node (ref "J1") (pin "12") (pinfunction "12_12") (pintype "passive"))
      (node (ref "U1") (pin "85") (pinfunction "ADC1_SE10/PTB4/ENET0_1588_TMR2/FTM1_FLT0_85") (pintype "bidirectional"))
    )
    (net (code "55") (name "/Y5") (class "Default")
      (node (ref "J1") (pin "13") (pinfunction "13_13") (pintype "passive"))
      (node (ref "U1") (pin "86") (pinfunction "ADC1_SE11/PTB5/ENET0_1588_TMR3/FTM2_FLT0_86") (pintype "bidirectional"))
    )
    (net (code "56") (name "/Y6") (class "Default")
      (node (ref "J1") (pin "14") (pinfunction "14_14") (pintype "passive"))
      (node (ref "U1") (pin "87") (pinfunction "ADC1_SE12/PTB6/FB_AD23_87") (pintype "bidirectional"))
    )
    (net (code "57") (name "/Y7") (class "Default")
      (node (ref "J1") (pin "15") (pinfunction "15_15") (pintype "passive"))
      (node (ref "U1") (pin "88") (pinfunction "ADC1_SE13/PTB7/FB_AD22_88") (pintype "bidirectional"))
    )
    (net (code "58") (name "CMOS_PWR_BUS") (class "Default")
      (node (ref "C37") (pin "2") (pinfunction "2_2") (pintype "passive"))
      (node (ref "C38") (pin "2") (pinfunction "2_2") (pintype "passive"))
      (node (ref "C50") (pin "1") (pinfunction "1_1") (pintype "passive"))
      (node (ref "C51") (pin "1") (pinfunction "1_1") (pintype "passive"))
      (node (ref "J1") (pin "17") (pinfunction "17_17") (pintype "passive"))
      (node (ref "J1") (pin "18") (pinfunction "18_18") (pintype "passive"))
      (node (ref "U5") (pin "5") (pinfunction "VOUT_5") (pintype "power_in"))
    )
    (net (code "59") (name "CORE_PWR") (class "Default")
      (node (ref "C16") (pin "2") (pinfunction "2_2") (pintype "passive"))
      (node (ref "C17") (pin "2") (pinfunction "2_2") (pintype "passive"))
      (node (ref "C41") (pin "2") (pinfunction "2_2") (pintype "passive"))
      (node (ref "C42") (pin "2") (pinfunction "2_2") (pintype "passive"))
      (node (ref "U1") (pin "31") (pinfunction "VDDA_31") (pintype "power_in"))
      (node (ref "U6") (pin "5") (pinfunction "VOUT_5") (pintype "power_in"))
      (node (ref "U7") (pin "1") (pinfunction "IN_1") (pintype "input"))
    )
    (net (code "60") (name "GND") (class "Default")
      (node (ref "ADCs1") (pin "2") (pinfunction "2_2") (pintype "passive"))
      (node (ref "C1") (pin "1") (pinfunction "1_1") (pintype "passive"))
      (node (ref "C10") (pin "1") (pinfunction "1_1") (pintype "passive"))
      (node (ref "C11") (pin "1") (pinfunction "1_1") (pintype "passive"))
      (node (ref "C12") (pin "2") (pinfunction "2_2") (pintype "passive"))
      (node (ref "C13") (pin "2") (pinfunction "2_2") (pintype "passive"))
      (node (ref "C14") (pin "2") (pinfunction "2_2") (pintype "passive"))
      (node (ref "C15") (pin "2") (pinfunction "2_2") (pintype "passive"))
      (node (ref "C19") (pin "2") (pinfunction "2_2") (pintype "passive"))
      (node (ref "C2") (pin "1") (pinfunction "1_1") (pintype "passive"))
      (node (ref "C20") (pin "2") (pinfunction "2_2") (pintype "passive"))
      (node (ref "C21") (pin "2") (pinfunction "2_2") (pintype "passive"))
      (node (ref "C22") (pin "1") (pinfunction "1_1") (pintype "passive"))
      (node (ref "C23") (pin "1") (pinfunction "1_1") (pintype "passive"))
      (node (ref "C24") (pin "1") (pinfunction "1_1") (pintype "passive"))
      (node (ref "C25") (pin "1") (pinfunction "1_1") (pintype "passive"))
      (node (ref "C26") (pin "1") (pinfunction "1_1") (pintype "passive"))
      (node (ref "C27") (pin "1") (pinfunction "1_1") (pintype "passive"))
      (node (ref "C28") (pin "1") (pinfunction "1_1") (pintype "passive"))
      (node (ref "C29") (pin "1") (pinfunction "1_1") (pintype "passive"))
      (node (ref "C3") (pin "1") (pinfunction "1_1") (pintype "passive"))
      (node (ref "C30") (pin "2") (pinfunction "2_2") (pintype "passive"))
      (node (ref "C31") (pin "1") (pinfunction "1_1") (pintype "passive"))
      (node (ref "C32") (pin "1") (pinfunction "1_1") (pintype "passive"))
      (node (ref "C33") (pin "1") (pinfunction "1_1") (pintype "passive"))
      (node (ref "C34") (pin "1") (pinfunction "1_1") (pintype "passive"))
      (node (ref "C35") (pin "1") (pinfunction "1_1") (pintype "passive"))
      (node (ref "C36") (pin "1") (pinfunction "1_1") (pintype "passive"))
      (node (ref "C37") (pin "1") (pinfunction "1_1") (pintype "passive"))
      (node (ref "C38") (pin "1") (pinfunction "1_1") (pintype "passive"))
      (node (ref "C39") (pin "1") (pinfunction "1_1") (pintype "passive"))
      (node (ref "C4") (pin "1") (pinfunction "1_1") (pintype "passive"))
      (node (ref "C40") (pin "1") (pinfunction "1_1") (pintype "passive"))
      (node (ref "C41") (pin "1") (pinfunction "1_1") (pintype "passive"))
      (node (ref "C42") (pin "1") (pinfunction "1_1") (pintype "passive"))
      (node (ref "C43") (pin "1") (pinfunction "1_1") (pintype "passive"))
      (node (ref "C5") (pin "1") (pinfunction "1_1") (pintype "passive"))
      (node (ref "C50") (pin "2") (pinfunction "2_2") (pintype "passive"))
      (node (ref "C51") (pin "2") (pinfunction "2_2") (pintype "passive"))
      (node (ref "C6") (pin "1") (pinfunction "1_1") (pintype "passive"))
      (node (ref "C7") (pin "1") (pinfunction "1_1") (pintype "passive"))
      (node (ref "C8") (pin "1") (pinfunction "1_1") (pintype "passive"))
      (node (ref "C9") (pin "1") (pinfunction "1_1") (pintype "passive"))
      (node (ref "GYRO1") (pin "1") (pinfunction "1_1") (pintype "passive"))
      (node (ref "GYRO1") (pin "5") (pinfunction "5_5") (pintype "passive"))
      (node (ref "J1") (pin "0") (pinfunction "0_0") (pintype "passive"))
      (node (ref "J1") (pin "16") (pinfunction "16_16") (pintype "passive"))
      (node (ref "J1") (pin "2") (pinfunction "2_2") (pintype "passive"))
      (node (ref "J1") (pin "7") (pinfunction "7_7") (pintype "passive"))
      (node (ref "JP1") (pin "2") (pinfunction "2_2") (pintype "passive"))
      (node (ref "JP2") (pin "1") (pinfunction "1_1") (pintype "passive"))
      (node (ref "JP3") (pin "1") (pinfunction "1_1") (pintype "passive"))
      (node (ref "JTAG1") (pin "3") (pinfunction "3_3") (pintype "passive"))
      (node (ref "K1") (pin "1") (pinfunction "1_1") (pintype "passive"))
      (node (ref "K2") (pin "5") (pintype "passive"))
      (node (ref "K3") (pin "2") (pinfunction "2_2") (pintype "passive"))
      (node (ref "K4") (pin "2") (pinfunction "2_2") (pintype "passive"))
      (node (ref "MCU1") (pin "2") (pinfunction "K_2") (pintype "passive"))
      (node (ref "OLED1") (pin "1") (pinfunction "1_1") (pintype "passive"))
      (node (ref "PWM1") (pin "5") (pinfunction "5_5") (pintype "passive"))
      (node (ref "PWR_SERVO1") (pin "2") (pinfunction "K_2") (pintype "passive"))
      (node (ref "Q1") (pin "2") (pinfunction "E_2") (pintype "passive"))
      (node (ref "R14") (pin "2") (pinfunction "2_2") (pintype "passive"))
      (node (ref "R5") (pin "2") (pinfunction "2_2") (pintype "passive"))
      (node (ref "R7") (pin "2") (pinfunction "2_2") (pintype "passive"))
      (node (ref "SERVO1") (pin "1") (pinfunction "1_1") (pintype "passive"))
      (node (ref "TF1") (pin "1") (pinfunction "1_1") (pintype "passive"))
      (node (ref "TF1") (pin "3") (pinfunction "3_3") (pintype "passive"))
      (node (ref "TF1") (pin "5") (pinfunction "5_5") (pintype "passive"))
      (node (ref "U1") (pin "107") (pinfunction "VSS4_107") (pintype "power_in"))
      (node (ref "U1") (pin "121") (pinfunction "VSS10_121") (pintype "power_in"))
      (node (ref "U1") (pin "134") (pinfunction "VSS7_134") (pintype "power_in"))
      (node (ref "U1") (pin "17") (pinfunction "VSS2_17") (pintype "power_in"))
      (node (ref "U1") (pin "18") (pinfunction "VSS8_18") (pintype "power_in"))
      (node (ref "U1") (pin "44") (pinfunction "VSS9_44") (pintype "power_in"))
      (node (ref "U1") (pin "57") (pinfunction "VSS5_57") (pintype "power_in"))
      (node (ref "U1") (pin "6") (pinfunction "VSS1_6") (pintype "power_in"))
      (node (ref "U1") (pin "71") (pinfunction "VSS6_71") (pintype "power_in"))
      (node (ref "U1") (pin "93") (pinfunction "VSS3_93") (pintype "power_in"))
      (node (ref "U2") (pin "3") (pinfunction "GND_3") (pintype "power_in"))
      (node (ref "U2") (pin "6") (pinfunction "GND_6") (pintype "power_in"))
      (node (ref "U3") (pin "3") (pinfunction "GND_3") (pintype "power_in"))
      (node (ref "U3") (pin "6") (pinfunction "GND_6") (pintype "power_in"))
      (node (ref "U4") (pin "2") (pinfunction "GND_2") (pintype "power_in"))
      (node (ref "U5") (pin "2") (pinfunction "GND_2") (pintype "power_in"))
      (node (ref "U6") (pin "2") (pinfunction "GND_2") (pintype "power_in"))
      (node (ref "X1") (pin "2") (pinfunction "GND_2") (pintype "passive"))
    )
    (net (code "61") (name "MCU_PWR") (class "Default")
      (node (ref "C10") (pin "2") (pinfunction "2_2") (pintype "passive"))
      (node (ref "C11") (pin "2") (pinfunction "2_2") (pintype "passive"))
      (node (ref "C3") (pin "2") (pinfunction "2_2") (pintype "passive"))
      (node (ref "C30") (pin "1") (pinfunction "1_1") (pintype "passive"))
      (node (ref "C4") (pin "2") (pinfunction "2_2") (pintype "passive"))
      (node (ref "C5") (pin "2") (pinfunction "2_2") (pintype "passive"))
      (node (ref "C6") (pin "2") (pinfunction "2_2") (pintype "passive"))
      (node (ref "C7") (pin "2") (pinfunction "2_2") (pintype "passive"))
      (node (ref "C8") (pin "2") (pinfunction "2_2") (pintype "passive"))
      (node (ref "C9") (pin "2") (pinfunction "2_2") (pintype "passive"))
      (node (ref "FB1") (pin "2") (pinfunction "2_2") (pintype "passive"))
      (node (ref "JTAG1") (pin "1") (pinfunction "1_1") (pintype "passive"))
      (node (ref "OLED1") (pin "2") (pinfunction "2_2") (pintype "passive"))
      (node (ref "R11") (pin "2") (pinfunction "2_2") (pintype "passive"))
      (node (ref "R4") (pin "1") (pinfunction "1_1") (pintype "passive"))
      (node (ref "U1") (pin "108") (pinfunction "VDD7_108") (pintype "power_in"))
      (node (ref "U1") (pin "122") (pinfunction "VDD8_122") (pintype "power_in"))
      (node (ref "U1") (pin "135") (pinfunction "VDD9_135") (pintype "power_in"))
      (node (ref "U1") (pin "16") (pinfunction "VDD2_16") (pintype "power_in"))
      (node (ref "U1") (pin "43") (pinfunction "VDD3_43") (pintype "power_in"))
      (node (ref "U1") (pin "5") (pinfunction "VDD1_5") (pintype "power_in"))
      (node (ref "U1") (pin "56") (pinfunction "VDD4_56") (pintype "power_in"))
      (node (ref "U1") (pin "70") (pinfunction "VDD5_70") (pintype "power_in"))
      (node (ref "U1") (pin "94") (pinfunction "VDD6_94") (pintype "power_in"))
    )
    (net (code "62") (name "MCU_PWR_BUS_3.3") (class "Default")
      (node (ref "C1") (pin "2") (pinfunction "2_2") (pintype "passive"))
      (node (ref "C2") (pin "2") (pinfunction "2_2") (pintype "passive"))
      (node (ref "C33") (pin "2") (pinfunction "2_2") (pintype "passive"))
      (node (ref "C34") (pin "2") (pinfunction "2_2") (pintype "passive"))
      (node (ref "FB1") (pin "1") (pinfunction "1_1") (pintype "passive"))
      (node (ref "U4") (pin "5") (pinfunction "VOUT_5") (pintype "power_in"))
      (node (ref "X1") (pin "4") (pinfunction "GND_4") (pintype "passive"))
    )
    (net (code "63") (name "Net-(LS1-K)") (class "Default")
      (node (ref "LS1") (pin "2") (pinfunction "K_2") (pintype "passive"))
      (node (ref "Q1") (pin "3") (pinfunction "C_3") (pintype "passive"))
    )
    (net (code "64") (name "Net-(MCU1-A)") (class "Default")
      (node (ref "MCU1") (pin "1") (pinfunction "A_1") (pintype "passive"))
      (node (ref "R4") (pin "2") (pinfunction "2_2") (pintype "passive"))
    )
    (net (code "65") (name "Net-(PWR_SERVO1-A)") (class "Default")
      (node (ref "PWR_SERVO1") (pin "1") (pinfunction "A_1") (pintype "passive"))
      (node (ref "R9") (pin "2") (pinfunction "2_2") (pintype "passive"))
    )
    (net (code "66") (name "Net-(Q1-B)") (class "Default")
      (node (ref "Q1") (pin "1") (pinfunction "B_1") (pintype "passive"))
      (node (ref "R15") (pin "2") (pinfunction "2_2") (pintype "passive"))
    )
    (net (code "67") (name "Net-(U2-ADJ)") (class "Default")
      (node (ref "R5") (pin "1") (pinfunction "1_1") (pintype "passive"))
      (node (ref "R6") (pin "1") (pinfunction "1_1") (pintype "passive"))
      (node (ref "U2") (pin "5") (pinfunction "ADJ_5") (pintype "passive"))
    )
    (net (code "68") (name "Net-(U3-ADJ)") (class "Default")
      (node (ref "R7") (pin "1") (pinfunction "1_1") (pintype "passive"))
      (node (ref "R8") (pin "1") (pinfunction "1_1") (pintype "passive"))
      (node (ref "U3") (pin "5") (pinfunction "ADJ_5") (pintype "passive"))
    )
    (net (code "69") (name "Net-(X1-OSC2)") (class "Default")
      (node (ref "R1") (pin "1") (pinfunction "1_1") (pintype "passive"))
      (node (ref "X1") (pin "3") (pinfunction "OSC2_3") (pintype "passive"))
    )
    (net (code "70") (name "PWR_BUS_5") (class "Default")
      (node (ref "ADCs1") (pin "1") (pinfunction "1_1") (pintype "passive"))
      (node (ref "C24") (pin "2") (pinfunction "2_2") (pintype "passive"))
      (node (ref "C25") (pin "2") (pinfunction "2_2") (pintype "passive"))
      (node (ref "C31") (pin "2") (pinfunction "2_2") (pintype "passive"))
      (node (ref "C32") (pin "2") (pinfunction "2_2") (pintype "passive"))
      (node (ref "C35") (pin "2") (pinfunction "2_2") (pintype "passive"))
      (node (ref "C36") (pin "2") (pinfunction "2_2") (pintype "passive"))
      (node (ref "C39") (pin "2") (pinfunction "2_2") (pintype "passive"))
      (node (ref "C40") (pin "2") (pinfunction "2_2") (pintype "passive"))
      (node (ref "GYRO1") (pin "4") (pinfunction "4_4") (pintype "passive"))
      (node (ref "JP1") (pin "1") (pinfunction "1_1") (pintype "passive"))
      (node (ref "JP2") (pin "2") (pinfunction "2_2") (pintype "passive"))
      (node (ref "JP3") (pin "2") (pinfunction "2_2") (pintype "passive"))
      (node (ref "LS1") (pin "1") (pinfunction "A_1") (pintype "passive"))
      (node (ref "R6") (pin "2") (pinfunction "2_2") (pintype "passive"))
      (node (ref "R9") (pin "1") (pinfunction "1_1") (pintype "passive"))
      (node (ref "TF1") (pin "10") (pinfunction "10_10") (pintype "passive"))
      (node (ref "U2") (pin "4") (pinfunction "OUT_4") (pintype "power_in"))
      (node (ref "U4") (pin "1") (pinfunction "VIN_1") (pintype "power_in"))
      (node (ref "U4") (pin "3") (pinfunction "EN_3") (pintype "input"))
      (node (ref "U5") (pin "1") (pinfunction "VIN_1") (pintype "power_in"))
      (node (ref "U5") (pin "3") (pinfunction "EN_3") (pintype "input"))
      (node (ref "U6") (pin "1") (pinfunction "VIN_1") (pintype "power_in"))
      (node (ref "U6") (pin "3") (pinfunction "EN_3") (pintype "input"))
    )
    (net (code "71") (name "PWR_BUS_6") (class "Default")
      (node (ref "C19") (pin "1") (pinfunction "1_1") (pintype "passive"))
      (node (ref "C28") (pin "2") (pinfunction "2_2") (pintype "passive"))
      (node (ref "C29") (pin "2") (pinfunction "2_2") (pintype "passive"))
      (node (ref "R8") (pin "2") (pinfunction "2_2") (pintype "passive"))
      (node (ref "SERVO1") (pin "2") (pinfunction "2_2") (pintype "passive"))
      (node (ref "U3") (pin "4") (pinfunction "OUT_4") (pintype "power_in"))
    )
    (net (code "72") (name "VBAT") (class "Default")
      (node (ref "C14") (pin "1") (pinfunction "1_1") (pintype "passive"))
      (node (ref "DRV1") (pin "1") (pintype "passive"))
      (node (ref "DRV1") (pin "2") (pintype "passive"))
      (node (ref "MBD1") (pin "1") (pintype "passive"))
      (node (ref "MBD1") (pin "2") (pintype "passive"))
    )
    (net (code "73") (name "VBRIDGE") (class "Default")
      (node (ref "C15") (pin "1") (pinfunction "1_1") (pintype "passive"))
      (node (ref "DRV1") (pin "3") (pintype "passive"))
    )
    (net (code "74") (name "VIN") (class "Default")
      (node (ref "C12") (pin "1") (pinfunction "1_1") (pintype "passive"))
      (node (ref "C13") (pin "1") (pinfunction "1_1") (pintype "passive"))
      (node (ref "C20") (pin "1") (pinfunction "1_1") (pintype "passive"))
      (node (ref "C21") (pin "1") (pinfunction "1_1") (pintype "passive"))
      (node (ref "C22") (pin "2") (pinfunction "2_2") (pintype "passive"))
      (node (ref "C23") (pin "2") (pinfunction "2_2") (pintype "passive"))
      (node (ref "C26") (pin "2") (pinfunction "2_2") (pintype "passive"))
      (node (ref "C27") (pin "2") (pinfunction "2_2") (pintype "passive"))
      (node (ref "MBD1") (pin "3") (pintype "passive"))
      (node (ref "U2") (pin "1") (pinfunction "~{SHDN}_1") (pintype "input"))
      (node (ref "U2") (pin "2") (pinfunction "IN_2") (pintype "power_in"))
      (node (ref "U3") (pin "1") (pinfunction "~{SHDN}_1") (pintype "input"))
      (node (ref "U3") (pin "2") (pinfunction "IN_2") (pintype "power_in"))
    )
    (net (code "75") (name "VSSA") (class "Default")
      (node (ref "C16") (pin "1") (pinfunction "1_1") (pintype "passive"))
      (node (ref "C17") (pin "1") (pinfunction "1_1") (pintype "passive"))
      (node (ref "NT1") (pin "2") (pinfunction "2_2") (pintype "passive"))
      (node (ref "R14") (pin "1") (pinfunction "1_1") (pintype "passive"))
      (node (ref "U1") (pin "34") (pinfunction "VSSA_34") (pintype "power_in"))
    )
    (net (code "76") (name "unconnected-(JP2-Pad5)") (class "Default")
      (node (ref "JP2") (pin "5") (pinfunction "5_5") (pintype "passive+no_connect"))
    )
    (net (code "77") (name "unconnected-(JP2-Pad6)") (class "Default")
      (node (ref "JP2") (pin "6") (pinfunction "6_6") (pintype "passive+no_connect"))
    )
    (net (code "78") (name "unconnected-(JP3-Pad5)") (class "Default")
      (node (ref "JP3") (pin "5") (pinfunction "5_5") (pintype "passive+no_connect"))
    )
    (net (code "79") (name "unconnected-(JP3-Pad6)") (class "Default")
      (node (ref "JP3") (pin "6") (pinfunction "6_6") (pintype "passive+no_connect"))
    )
    (net (code "80") (name "unconnected-(K1-Pad3)") (class "Default")
      (node (ref "K1") (pin "3") (pinfunction "3_3") (pintype "passive+no_connect"))
    )
    (net (code "81") (name "unconnected-(K1-Pad4)") (class "Default")
      (node (ref "K1") (pin "4") (pinfunction "4_4") (pintype "passive+no_connect"))
    )
    (net (code "82") (name "unconnected-(K2-Pad2)") (class "Default")
      (node (ref "K2") (pin "2") (pintype "passive"))
    )
    (net (code "83") (name "unconnected-(LS1-NC-Pad3)") (class "Default")
      (node (ref "LS1") (pin "3") (pinfunction "NC_3") (pintype "passive+no_connect"))
    )
    (net (code "84") (name "unconnected-(LS1-NC-Pad4)") (class "Default")
      (node (ref "LS1") (pin "4") (pinfunction "NC_4") (pintype "passive+no_connect"))
    )
    (net (code "85") (name "unconnected-(U1-ADC0_DM1-Pad24)") (class "Default")
      (node (ref "U1") (pin "24") (pinfunction "ADC0_DM1_24") (pintype "bidirectional+no_connect"))
    )
    (net (code "86") (name "unconnected-(U1-ADC0_DP1-Pad23)") (class "Default")
      (node (ref "U1") (pin "23") (pinfunction "ADC0_DP1_23") (pintype "bidirectional+no_connect"))
    )
    (net (code "87") (name "unconnected-(U1-ADC0_SE4b{slash}CMP1_IN0{slash}TSI0_CH15{slash}PTC2{slash}SPI0_PCS2{slash}~{UART1_CTS}{slash}FTM0_CH1{slash}FB_AD12-Pad105)") (class "Default")
      (node (ref "U1") (pin "105") (pinfunction "ADC0_SE4b/CMP1_IN0/TSI0_CH15/PTC2/SPI0_PCS2/~{UART1_CTS}/FTM0_CH1/FB_AD12_105") (pintype "bidirectional+no_connect"))
    )
    (net (code "88") (name "unconnected-(U1-ADC0_SE5b{slash}PTD1{slash}SPI0_SCK{slash}~{UART2_CTS}{slash}~{FB_CS0}-Pad128)") (class "Default")
      (node (ref "U1") (pin "128") (pinfunction "ADC0_SE5b/PTD1/SPI0_SCK/~{UART2_CTS}/~{FB_CS0}_128") (pintype "bidirectional+no_connect"))
    )
    (net (code "89") (name "unconnected-(U1-ADC0_SE6b{slash}PTD5{slash}SPI0_PCS2{slash}~{UART0_CTS}{slash}FTM0_CH5{slash}FB_AD1{slash}~{EWM_OUT}-Pad132)") (class "Default")
      (node (ref "U1") (pin "132") (pinfunction "ADC0_SE6b/PTD5/SPI0_PCS2/~{UART0_CTS}/FTM0_CH5/FB_AD1/~{EWM_OUT}_132") (pintype "bidirectional+no_connect"))
    )
    (net (code "90") (name "unconnected-(U1-ADC0_SE7b{slash}PTD6{slash}SPI0_PCS3{slash}UART0_RX{slash}FTM0_CH6{slash}FB_AD0{slash}FTM0_FLT0-Pad133)") (class "Default")
      (node (ref "U1") (pin "133") (pinfunction "ADC0_SE7b/PTD6/SPI0_PCS3/UART0_RX/FTM0_CH6/FB_AD0/FTM0_FLT0_133") (pintype "bidirectional+no_connect"))
    )
    (net (code "91") (name "unconnected-(U1-ADC0_SE10{slash}PTA7{slash}FTM0_CH4{slash}TRACE_D3-Pad59)") (class "Default")
      (node (ref "U1") (pin "59") (pinfunction "ADC0_SE10/PTA7/FTM0_CH4/TRACE_D3_59") (pintype "bidirectional+no_connect"))
    )
    (net (code "92") (name "unconnected-(U1-ADC0_SE14{slash}TSI0_CH13{slash}PTC0{slash}SPI0_PCS4{slash}PDB0_EXTRG{slash}I2S0_TXD{slash}FB_AD14-Pad103)") (class "Default")
      (node (ref "U1") (pin "103") (pinfunction "ADC0_SE14/TSI0_CH13/PTC0/SPI0_PCS4/PDB0_EXTRG/I2S0_TXD/FB_AD14_103") (pintype "bidirectional+no_connect"))
    )
    (net (code "93") (name "unconnected-(U1-ADC0_SE15{slash}TSI0_CH14{slash}PTC1{slash}SPI0_PCS3{slash}~{UART1_RTS}{slash}FTM0_CH0{slash}FB_AD13-Pad104)") (class "Default")
      (node (ref "U1") (pin "104") (pinfunction "ADC0_SE15/TSI0_CH14/PTC1/SPI0_PCS3/~{UART1_RTS}/FTM0_CH0/FB_AD13_104") (pintype "bidirectional+no_connect"))
    )
    (net (code "94") (name "unconnected-(U1-ADC1_DM1-Pad26)") (class "Default")
      (node (ref "U1") (pin "26") (pinfunction "ADC1_DM1_26") (pintype "bidirectional+no_connect"))
    )
    (net (code "95") (name "unconnected-(U1-ADC1_DP1-Pad25)") (class "Default")
      (node (ref "U1") (pin "25") (pinfunction "ADC1_DP1_25") (pintype "bidirectional+no_connect"))
    )
    (net (code "96") (name "unconnected-(U1-ADC1_SE17{slash}PTA17{slash}SPI0_SIN{slash}~{UART0_RTS}{slash}RMII0_TXD1{slash}MII0_TXD1{slash}I2S0_MCLK{slash}I2S0_CLKIN-Pad69)") (class "Default")
      (node (ref "U1") (pin "69") (pinfunction "ADC1_SE17/PTA17/SPI0_SIN/~{UART0_RTS}/RMII0_TXD1/MII0_TXD1/I2S0_MCLK/I2S0_CLKIN_69") (pintype "bidirectional+no_connect"))
    )
    (net (code "97") (name "unconnected-(U1-CMP0_IN1{slash}PTC7{slash}SPI0_SIN{slash}FB_AD8-Pad112)") (class "Default")
      (node (ref "U1") (pin "112") (pinfunction "CMP0_IN1/PTC7/SPI0_SIN/FB_AD8_112") (pintype "bidirectional+no_connect"))
    )
    (net (code "98") (name "unconnected-(U1-CMP1_IN1{slash}PTC3{slash}SPI0_PCS1{slash}UART1_RX{slash}FTM0_CH2{slash}FB_CLKOUT-Pad106)") (class "Default")
      (node (ref "U1") (pin "106") (pinfunction "CMP1_IN1/PTC3/SPI0_PCS1/UART1_RX/FTM0_CH2/FB_CLKOUT_106") (pintype "bidirectional+no_connect"))
    )
    (net (code "99") (name "unconnected-(U1-CMP2_IN0{slash}PTA12{slash}CAN0_TX{slash}FTM1_CH0{slash}RMII0_RXD1{slash}MII0_RXD1{slash}I2S0_TXD{slash}FTM1_QD_PHA-Pad64)") (class "Default")
      (node (ref "U1") (pin "64") (pinfunction "CMP2_IN0/PTA12/CAN0_TX/FTM1_CH0/RMII0_RXD1/MII0_RXD1/I2S0_TXD/FTM1_QD_PHA_64") (pintype "bidirectional+no_connect"))
    )
    (net (code "100") (name "unconnected-(U1-CMP2_IN1{slash}PTA13{slash}CAN0_RX{slash}FTM1_CH1{slash}RMII0_RXD0{slash}MII0_RXD0{slash}I2S0_TX_FS{slash}FTM1_QD_PHB-Pad65)") (class "Default")
      (node (ref "U1") (pin "65") (pinfunction "CMP2_IN1/PTA13/CAN0_RX/FTM1_CH1/RMII0_RXD0/MII0_RXD0/I2S0_TX_FS/FTM1_QD_PHB_65") (pintype "bidirectional+no_connect"))
    )
    (net (code "101") (name "unconnected-(U1-DAC0_OUT-Pad38)") (class "Default")
      (node (ref "U1") (pin "38") (pinfunction "DAC0_OUT_38") (pintype "bidirectional+no_connect"))
    )
    (net (code "102") (name "unconnected-(U1-EXTAL32-Pad41)") (class "Default")
      (node (ref "U1") (pin "41") (pinfunction "EXTAL32_41") (pintype "input+no_connect"))
    )
    (net (code "103") (name "unconnected-(U1-JTAG_TDI{slash}EZP_DI{slash}TSI0_CH2{slash}PTA1{slash}UART0_RX{slash}FTM0_CH6-Pad51)") (class "Default")
      (node (ref "U1") (pin "51") (pinfunction "JTAG_TDI/EZP_DI/TSI0_CH2/PTA1/UART0_RX/FTM0_CH6_51") (pintype "bidirectional+no_connect"))
    )
    (net (code "104") (name "unconnected-(U1-JTAG_TDO{slash}TRACE_SWO{slash}EZP_DO{slash}TSI0_CH3{slash}PTA2{slash}UART0_TX{slash}FTM0_CH7-Pad52)") (class "Default")
      (node (ref "U1") (pin "52") (pinfunction "JTAG_TDO/TRACE_SWO/EZP_DO/TSI0_CH3/PTA2/UART0_TX/FTM0_CH7_52") (pintype "bidirectional+no_connect"))
    )
    (net (code "105") (name "unconnected-(U1-JTAG_TRST{slash}PTA5{slash}FTM0_CH2{slash}RMII0_RXER{slash}MII0_RXER{slash}CMP2_OUT{slash}I2S0_RX_BCLK-Pad55)") (class "Default")
      (node (ref "U1") (pin "55") (pinfunction "JTAG_TRST/PTA5/FTM0_CH2/RMII0_RXER/MII0_RXER/CMP2_OUT/I2S0_RX_BCLK_55") (pintype "bidirectional+no_connect"))
    )
    (net (code "106") (name "unconnected-(U1-PGA0_DP{slash}ADC0_DP0{slash}ADC1_DP3-Pad27)") (class "Default")
      (node (ref "U1") (pin "27") (pinfunction "PGA0_DP/ADC0_DP0/ADC1_DP3_27") (pintype "bidirectional+no_connect"))
    )
    (net (code "107") (name "unconnected-(U1-PGA1_DM{slash}ADC1_DM0{slash}ADC0_DM3-Pad30)") (class "Default")
      (node (ref "U1") (pin "30") (pinfunction "PGA1_DM/ADC1_DM0/ADC0_DM3_30") (pintype "bidirectional+no_connect"))
    )
    (net (code "108") (name "unconnected-(U1-PGA1_DP{slash}ADC1_DP0{slash}ADC0_DP3-Pad29)") (class "Default")
      (node (ref "U1") (pin "29") (pinfunction "PGA1_DP/ADC1_DP0/ADC0_DP3_29") (pintype "bidirectional+no_connect"))
    )
    (net (code "109") (name "unconnected-(U1-PTA6{slash}FTM0_CH3{slash}TRACE_CLKOUT-Pad58)") (class "Default")
      (node (ref "U1") (pin "58") (pinfunction "PTA6/FTM0_CH3/TRACE_CLKOUT_58") (pintype "bidirectional+no_connect"))
    )
    (net (code "110") (name "unconnected-(U1-PTA14{slash}SPI0_PCS0{slash}UART0_TX{slash}RMII0_CRS_DV{slash}MII0_RXDV{slash}I2S0_TX_BCLK-Pad66)") (class "Default")
      (node (ref "U1") (pin "66") (pinfunction "PTA14/SPI0_PCS0/UART0_TX/RMII0_CRS_DV/MII0_RXDV/I2S0_TX_BCLK_66") (pintype "bidirectional+no_connect"))
    )
    (net (code "111") (name "unconnected-(U1-PTA15{slash}SPI0_SCK{slash}UART0_RX{slash}RMII0_TXEN{slash}MII0_TXEN{slash}I2S0_RXD-Pad67)") (class "Default")
      (node (ref "U1") (pin "67") (pinfunction "PTA15/SPI0_SCK/UART0_RX/RMII0_TXEN/MII0_TXEN/I2S0_RXD_67") (pintype "bidirectional+no_connect"))
    )
    (net (code "112") (name "unconnected-(U1-PTA16{slash}SPI0_SOUT{slash}~{UART0_CTS}{slash}RMII0_TXD0{slash}MII0_TXD0{slash}I2S0_RX_FS-Pad68)") (class "Default")
      (node (ref "U1") (pin "68") (pinfunction "PTA16/SPI0_SOUT/~{UART0_CTS}/RMII0_TXD0/MII0_TXD0/I2S0_RX_FS_68") (pintype "bidirectional+no_connect"))
    )
    (net (code "113") (name "unconnected-(U1-PTA24{slash}MII0_TXD2{slash}FB_A29-Pad75)") (class "Default")
      (node (ref "U1") (pin "75") (pinfunction "PTA24/MII0_TXD2/FB_A29_75") (pintype "bidirectional+no_connect"))
    )
    (net (code "114") (name "unconnected-(U1-PTA27{slash}MII0_CRS{slash}FB_A26-Pad78)") (class "Default")
      (node (ref "U1") (pin "78") (pinfunction "PTA27/MII0_CRS/FB_A26_78") (pintype "bidirectional+no_connect"))
    )
    (net (code "115") (name "unconnected-(U1-PTA28{slash}MII0_TXER{slash}FB_A25-Pad79)") (class "Default")
      (node (ref "U1") (pin "79") (pinfunction "PTA28/MII0_TXER/FB_A25_79") (pintype "bidirectional+no_connect"))
    )
    (net (code "116") (name "unconnected-(U1-PTA29{slash}MII0_COL{slash}FB_A24-Pad80)") (class "Default")
      (node (ref "U1") (pin "80") (pinfunction "PTA29/MII0_COL/FB_A24_80") (pintype "bidirectional+no_connect"))
    )
    (net (code "117") (name "unconnected-(U1-PTB8{slash}~{UART3_RTS}{slash}FB_AD21-Pad89)") (class "Default")
      (node (ref "U1") (pin "89") (pinfunction "PTB8/~{UART3_RTS}/FB_AD21_89") (pintype "bidirectional+no_connect"))
    )
    (net (code "118") (name "unconnected-(U1-PTB23{slash}SPI2_SIN{slash}SPI0_PCS5{slash}FB_AD28-Pad102)") (class "Default")
      (node (ref "U1") (pin "102") (pinfunction "PTB23/SPI2_SIN/SPI0_PCS5/FB_AD28_102") (pintype "bidirectional+no_connect"))
    )
    (net (code "119") (name "unconnected-(U1-PTC4{slash}SPI0_PCS0{slash}UART1_TX{slash}FTM0_CH3{slash}FB_AD11{slash}CMP1_OUT-Pad109)") (class "Default")
      (node (ref "U1") (pin "109") (pinfunction "PTC4/SPI0_PCS0/UART1_TX/FTM0_CH3/FB_AD11/CMP1_OUT_109") (pintype "bidirectional+no_connect"))
    )
    (net (code "120") (name "unconnected-(U1-PTD0{slash}SPI0_PCS0{slash}~{UART2_RTS}{slash}FB_ALE{slash}~{FB_CS1}{slash}~{FB_TS}-Pad127)") (class "Default")
      (node (ref "U1") (pin "127") (pinfunction "PTD0/SPI0_PCS0/~{UART2_RTS}/FB_ALE/~{FB_CS1}/~{FB_TS}_127") (pintype "bidirectional+no_connect"))
    )
    (net (code "121") (name "unconnected-(U1-PTD2{slash}SPI0_SOUT{slash}UART2_RX{slash}FB_AD4-Pad129)") (class "Default")
      (node (ref "U1") (pin "129") (pinfunction "PTD2/SPI0_SOUT/UART2_RX/FB_AD4_129") (pintype "bidirectional+no_connect"))
    )
    (net (code "122") (name "unconnected-(U1-PTD3{slash}SPI0_SIN{slash}UART2_TX{slash}FB_AD3-Pad130)") (class "Default")
      (node (ref "U1") (pin "130") (pinfunction "PTD3/SPI0_SIN/UART2_TX/FB_AD3_130") (pintype "bidirectional+no_connect"))
    )
    (net (code "123") (name "unconnected-(U1-PTD4{slash}SPI0_PCS1{slash}~{UART0_RTS}{slash}FTM0_CH4{slash}FB_AD2{slash}EWM_IN-Pad131)") (class "Default")
      (node (ref "U1") (pin "131") (pinfunction "PTD4/SPI0_PCS1/~{UART0_RTS}/FTM0_CH4/FB_AD2/EWM_IN_131") (pintype "bidirectional+no_connect"))
    )
    (net (code "124") (name "unconnected-(U1-PTD10{slash}~{UART5_RTS}{slash}FB_A18-Pad139)") (class "Default")
      (node (ref "U1") (pin "139") (pinfunction "PTD10/~{UART5_RTS}/FB_A18_139") (pintype "bidirectional+no_connect"))
    )
    (net (code "125") (name "unconnected-(U1-PTD11{slash}SPI2_PCS0{slash}~{UART5_CTS}{slash}SDHC0_CLKIN{slash}FB_A19-Pad140)") (class "Default")
      (node (ref "U1") (pin "140") (pinfunction "PTD11/SPI2_PCS0/~{UART5_CTS}/SDHC0_CLKIN/FB_A19_140") (pintype "bidirectional+no_connect"))
    )
    (net (code "126") (name "unconnected-(U1-PTD14{slash}SPI2_SIN{slash}SDHC0_D6{slash}FB_A22-Pad143)") (class "Default")
      (node (ref "U1") (pin "143") (pinfunction "PTD14/SPI2_SIN/SDHC0_D6/FB_A22_143") (pintype "bidirectional+no_connect"))
    )
    (net (code "127") (name "unconnected-(U1-PTD15{slash}SPI2_PCS1{slash}SDHC0_D7{slash}FB_A23-Pad144)") (class "Default")
      (node (ref "U1") (pin "144") (pinfunction "PTD15/SPI2_PCS1/SDHC0_D7/FB_A23_144") (pintype "bidirectional+no_connect"))
    )
    (net (code "128") (name "unconnected-(U1-PTE6{slash}SPI1_PCS3{slash}~{UART3_CTS}{slash}I2S0_MCLK{slash}I2S0_CLKIN-Pad9)") (class "Default")
      (node (ref "U1") (pin "9") (pinfunction "PTE6/SPI1_PCS3/~{UART3_CTS}/I2S0_MCLK/I2S0_CLKIN_9") (pintype "bidirectional+no_connect"))
    )
    (net (code "129") (name "unconnected-(U1-PTE7{slash}~{UART3_RTS}{slash}I2S0_RXD-Pad10)") (class "Default")
      (node (ref "U1") (pin "10") (pinfunction "PTE7/~{UART3_RTS}/I2S0_RXD_10") (pintype "bidirectional+no_connect"))
    )
    (net (code "130") (name "unconnected-(U1-PTE8{slash}UART5_TX{slash}I2S0_RX_FS-Pad11)") (class "Default")
      (node (ref "U1") (pin "11") (pinfunction "PTE8/UART5_TX/I2S0_RX_FS_11") (pintype "bidirectional+no_connect"))
    )
    (net (code "131") (name "unconnected-(U1-PTE9{slash}UART5_RX{slash}I2S0_RX_BCLK-Pad12)") (class "Default")
      (node (ref "U1") (pin "12") (pinfunction "PTE9/UART5_RX/I2S0_RX_BCLK_12") (pintype "bidirectional+no_connect"))
    )
    (net (code "132") (name "unconnected-(U1-PTE10{slash}~{UART5_CTS}{slash}I2S0_TXD-Pad13)") (class "Default")
      (node (ref "U1") (pin "13") (pinfunction "PTE10/~{UART5_CTS}/I2S0_TXD_13") (pintype "bidirectional+no_connect"))
    )
    (net (code "133") (name "unconnected-(U1-PTE11{slash}~{UART5_RTS}{slash}I2S0_TX_FS-Pad14)") (class "Default")
      (node (ref "U1") (pin "14") (pinfunction "PTE11/~{UART5_RTS}/I2S0_TX_FS_14") (pintype "bidirectional+no_connect"))
    )
    (net (code "134") (name "unconnected-(U1-PTE12{slash}I2S0_TX_BCLK-Pad15)") (class "Default")
      (node (ref "U1") (pin "15") (pinfunction "PTE12/I2S0_TX_BCLK_15") (pintype "bidirectional+no_connect"))
    )
    (net (code "135") (name "unconnected-(U1-PTE26{slash}~{UART4_CTS}{slash}ENET_1588_CLKIN{slash}RTC_CLKOUT{slash}USB_CLKIN-Pad47)") (class "Default")
      (node (ref "U1") (pin "47") (pinfunction "PTE26/~{UART4_CTS}/ENET_1588_CLKIN/RTC_CLKOUT/USB_CLKIN_47") (pintype "bidirectional+no_connect"))
    )
    (net (code "136") (name "unconnected-(U1-PTE27{slash}~{UART4_RTS}-Pad48)") (class "Default")
      (node (ref "U1") (pin "48") (pinfunction "PTE27/~{UART4_RTS}_48") (pintype "bidirectional+no_connect"))
    )
    (net (code "137") (name "unconnected-(U1-PTE28-Pad49)") (class "Default")
      (node (ref "U1") (pin "49") (pinfunction "PTE28_49") (pintype "bidirectional+no_connect"))
    )
    (net (code "138") (name "unconnected-(U1-TSI0_CH9{slash}PTB16{slash}SPI1_SOUT{slash}UART0_RX{slash}FB_AD17{slash}EWM_IN-Pad95)") (class "Default")
      (node (ref "U1") (pin "95") (pinfunction "TSI0_CH9/PTB16/SPI1_SOUT/UART0_RX/FB_AD17/EWM_IN_95") (pintype "bidirectional+no_connect"))
    )
    (net (code "139") (name "unconnected-(U1-TSI0_CH10{slash}PTB17{slash}SPI1_SIN{slash}UART0_TX{slash}FB_AD16{slash}~{EWM_OUT}-Pad96)") (class "Default")
      (node (ref "U1") (pin "96") (pinfunction "TSI0_CH10/PTB17/SPI1_SIN/UART0_TX/FB_AD16/~{EWM_OUT}_96") (pintype "bidirectional+no_connect"))
    )
    (net (code "140") (name "unconnected-(U1-TSI0_CH11{slash}PTB18{slash}CAN0_TX{slash}FTM2_CH0{slash}I2S0_TX_BCLK{slash}FB_AD15{slash}FTM2_QD_PHA-Pad97)") (class "Default")
      (node (ref "U1") (pin "97") (pinfunction "TSI0_CH11/PTB18/CAN0_TX/FTM2_CH0/I2S0_TX_BCLK/FB_AD15/FTM2_QD_PHA_97") (pintype "bidirectional+no_connect"))
    )
    (net (code "141") (name "unconnected-(U1-TSI0_CH12{slash}PTB19{slash}CAN0_RX{slash}FTM2_CH1{slash}I2S0_TX_FS{slash}~{FB_OE}{slash}FTM2_QD_PHB-Pad98)") (class "Default")
      (node (ref "U1") (pin "98") (pinfunction "TSI0_CH12/PTB19/CAN0_RX/FTM2_CH1/I2S0_TX_FS/~{FB_OE}/FTM2_QD_PHB_98") (pintype "bidirectional+no_connect"))
    )
    (net (code "142") (name "unconnected-(U1-USB0_DM-Pad20)") (class "Default")
      (node (ref "U1") (pin "20") (pinfunction "USB0_DM_20") (pintype "bidirectional+no_connect"))
    )
    (net (code "143") (name "unconnected-(U1-USB0_DP-Pad19)") (class "Default")
      (node (ref "U1") (pin "19") (pinfunction "USB0_DP_19") (pintype "bidirectional+no_connect"))
    )
    (net (code "144") (name "unconnected-(U1-VBAT-Pad42)") (class "Default")
      (node (ref "U1") (pin "42") (pinfunction "VBAT_42") (pintype "power_in+no_connect"))
    )
    (net (code "145") (name "unconnected-(U1-VOUT33-Pad21)") (class "Default")
      (node (ref "U1") (pin "21") (pinfunction "VOUT33_21") (pintype "power_in+no_connect"))
    )
    (net (code "146") (name "unconnected-(U1-VREF_OUT-Pad37)") (class "Default")
      (node (ref "U1") (pin "37") (pinfunction "VREF_OUT_37") (pintype "power_in+no_connect"))
    )
    (net (code "147") (name "unconnected-(U1-VREGIN-Pad22)") (class "Default")
      (node (ref "U1") (pin "22") (pinfunction "VREGIN_22") (pintype "power_in+no_connect"))
    )
    (net (code "148") (name "unconnected-(U1-XTAL32-Pad40)") (class "Default")
      (node (ref "U1") (pin "40") (pinfunction "XTAL32_40") (pintype "output+no_connect"))
    )
    (net (code "149") (name "unconnected-(U1-XTAL{slash}PTA19{slash}FTM1_FLT0{slash}FTM_CLKIN1{slash}LPT0_ALT1-Pad73)") (class "Default")
      (node (ref "U1") (pin "73") (pinfunction "XTAL/PTA19/FTM1_FLT0/FTM_CLKIN1/LPT0_ALT1_73") (pintype "bidirectional+no_connect"))
    )
    (net (code "150") (name "unconnected-(U1-~{NMI}{slash}~{EZP_CS}{slash}TSI0_CH~{5}PTA~{4}FTM0_CH1-Pad54)") (class "Default")
      (node (ref "U1") (pin "54") (pinfunction "~{NMI}/~{EZP_CS}/TSI0_CH~{5}PTA~{4}FTM0_CH1_54") (pintype "bidirectional+no_connect"))
    )
    (net (code "151") (name "unconnected-(U4-NC-Pad4)") (class "Default")
      (node (ref "U4") (pin "4") (pinfunction "NC_4") (pintype "passive+no_connect"))
    )
    (net (code "152") (name "unconnected-(U5-NC-Pad4)") (class "Default")
      (node (ref "U5") (pin "4") (pinfunction "NC_4") (pintype "passive+no_connect"))
    )
    (net (code "153") (name "unconnected-(U6-NC-Pad4)") (class "Default")
      (node (ref "U6") (pin "4") (pinfunction "NC_4") (pintype "passive+no_connect"))
    )
    (net (code "154") (name "unconnected-(X1-OSC1-Pad1)") (class "Default")
      (node (ref "X1") (pin "1") (pinfunction "OSC1_1") (pintype "passive+no_connect"))
    )
  )
)
